# MGC3130_Board.net
KiCad netlist of a schematic drawn in EAGLE
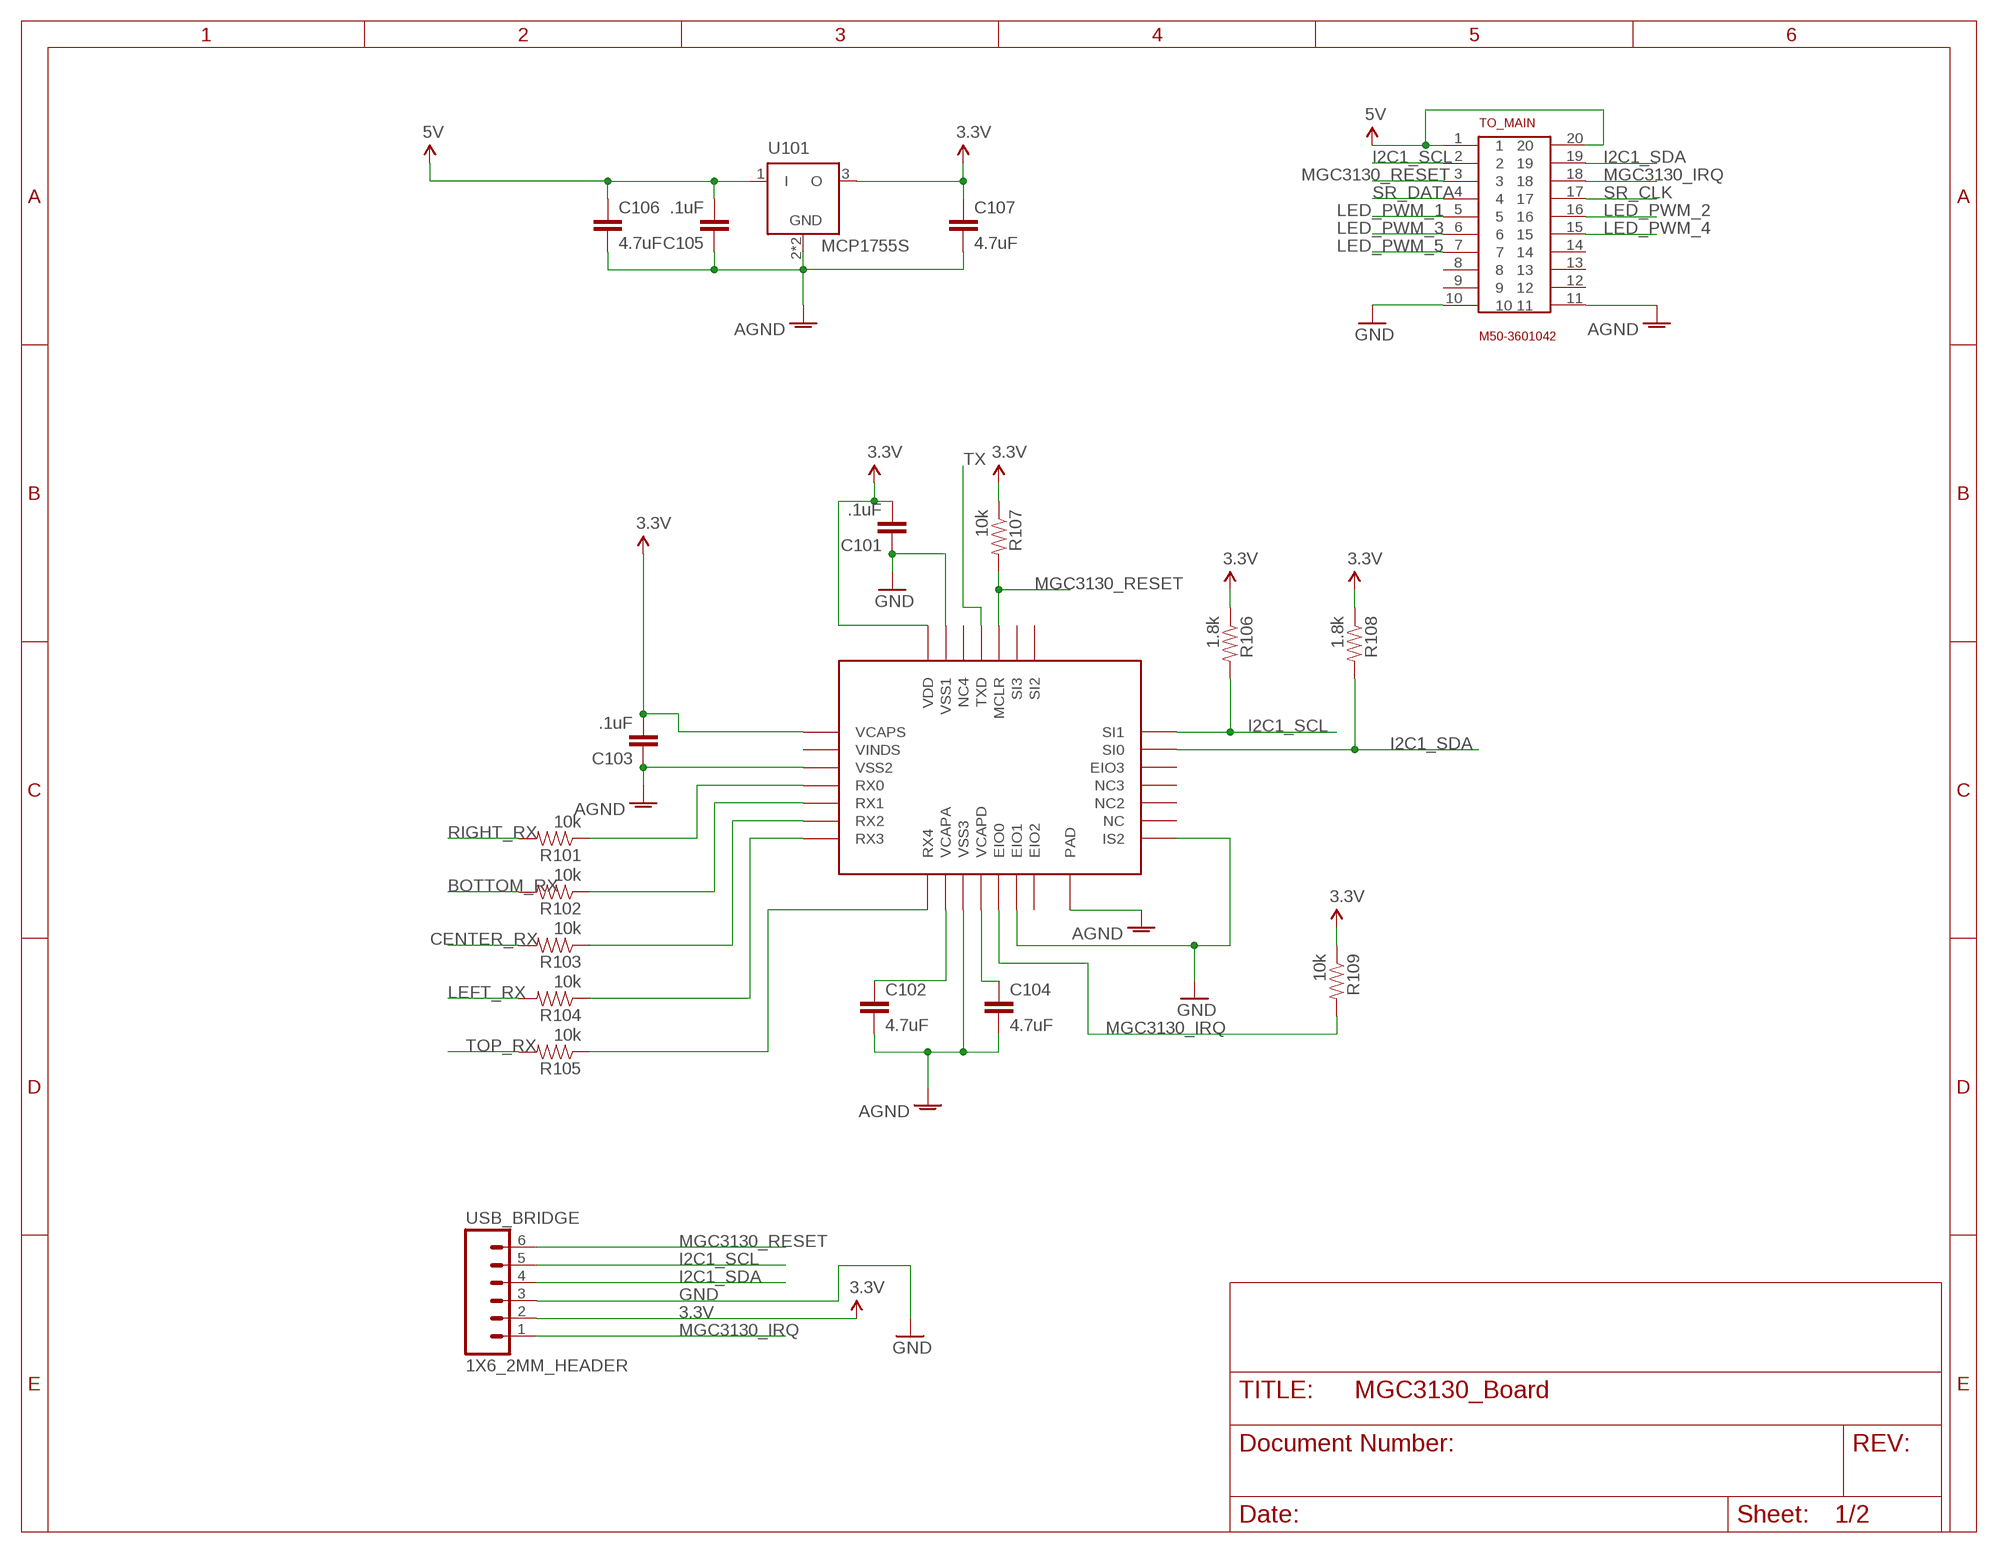
[diagram p0: schematic, sheet 1]
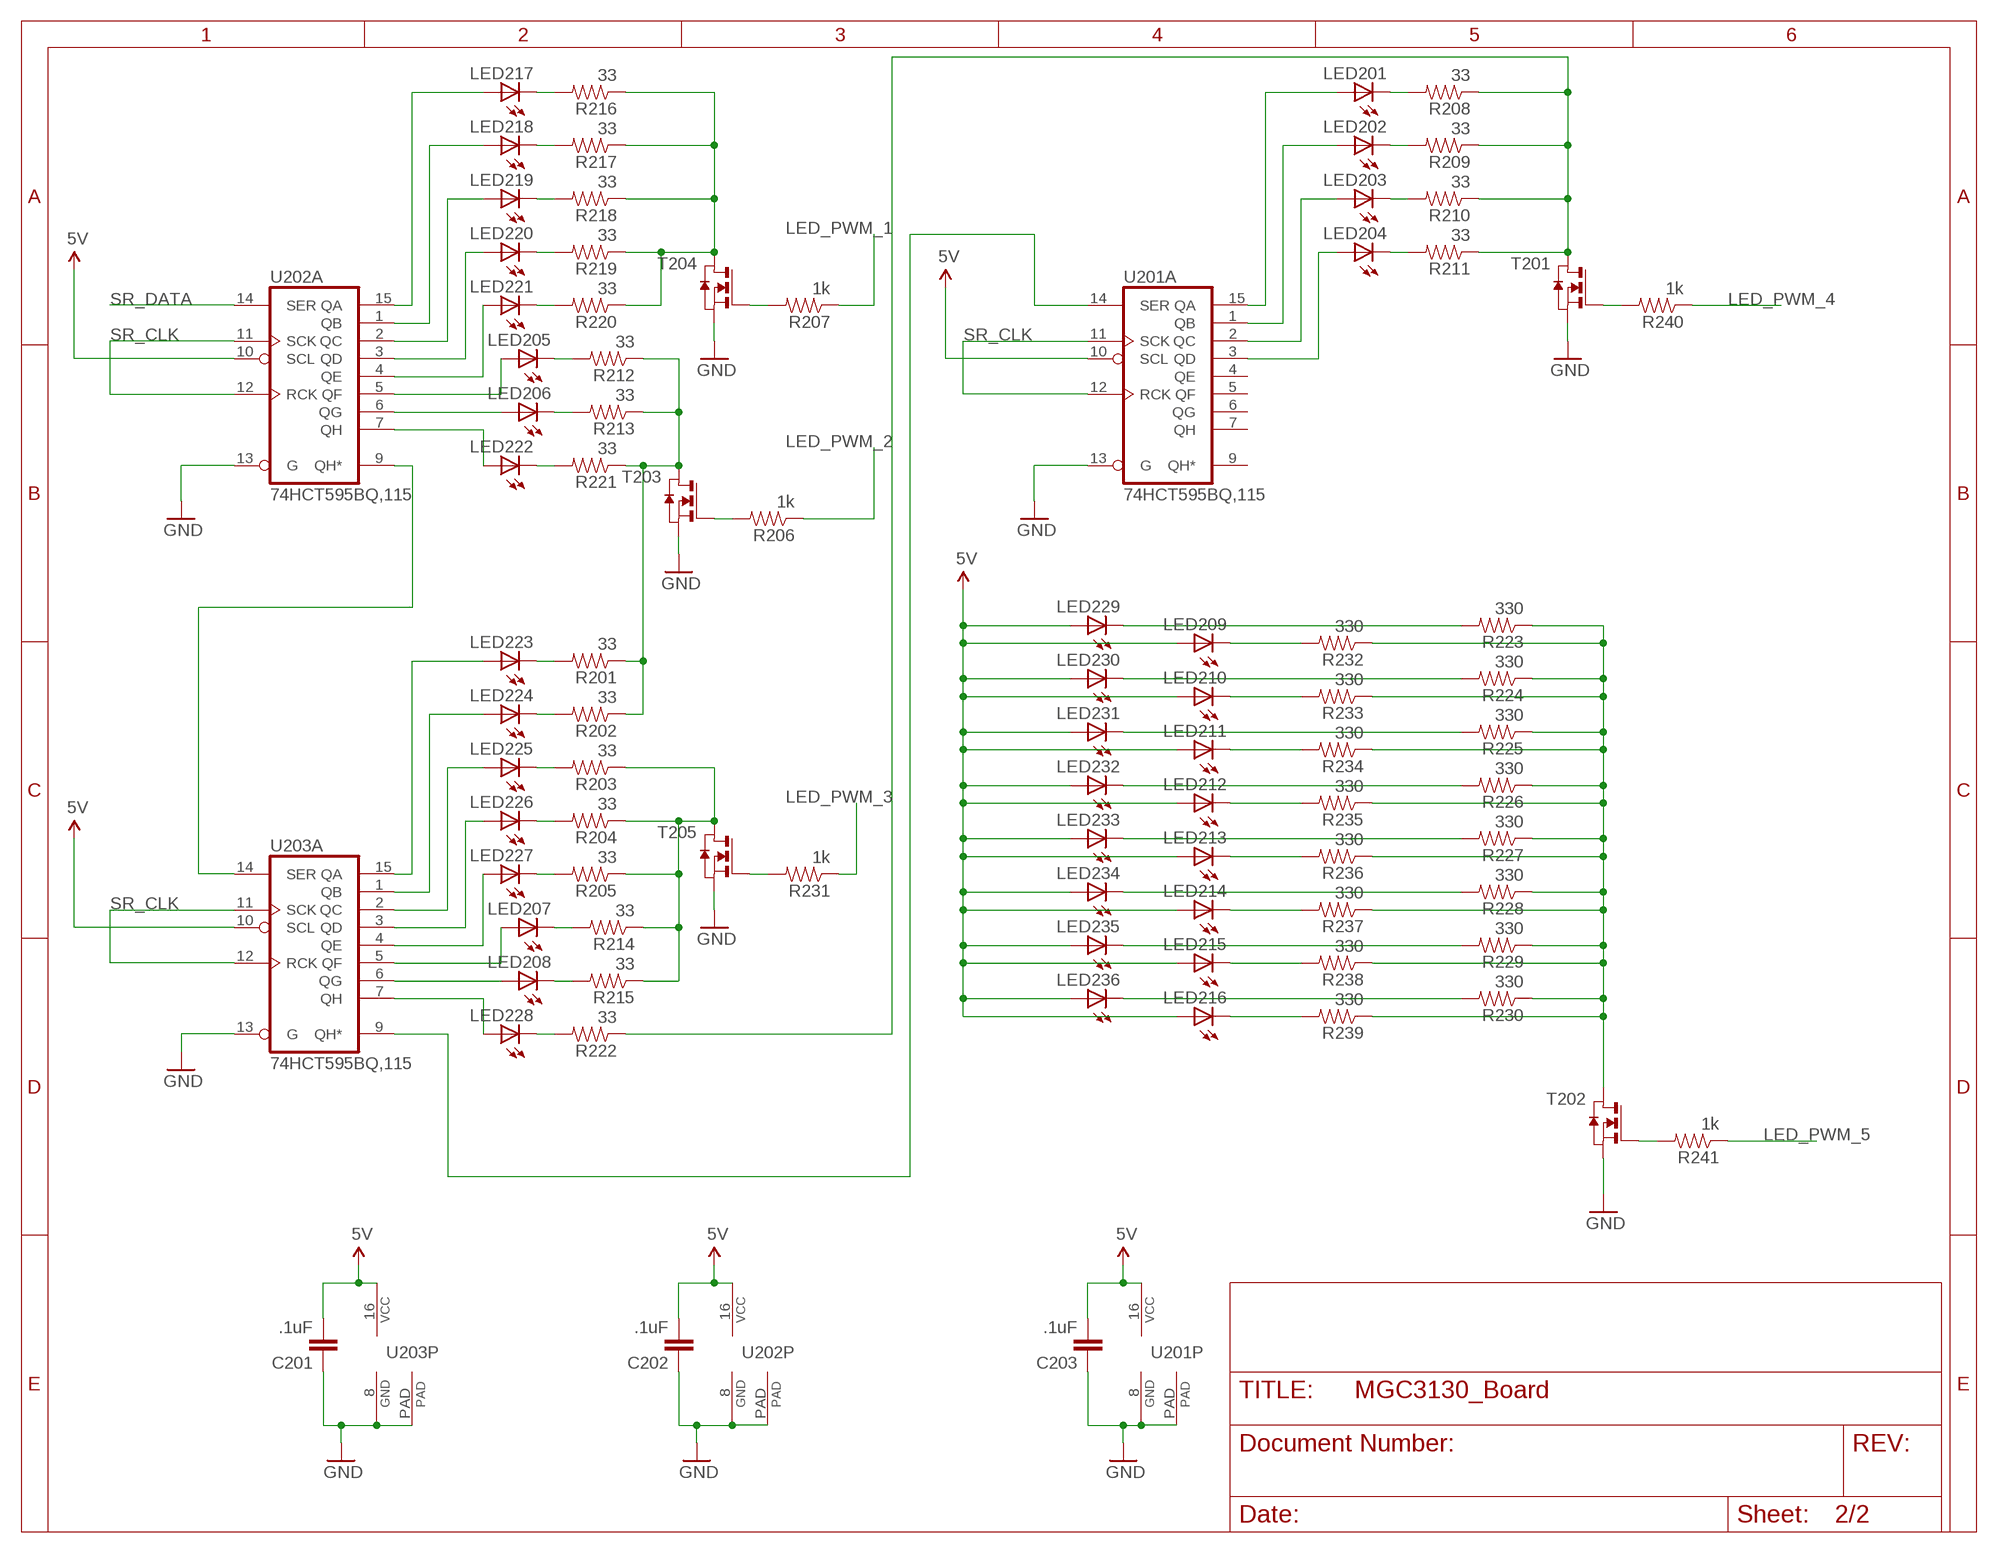
[diagram p1: schematic, sheet 2]

(export (version "E")
  (design (tool "Eeschema 10.0.6"))
  (components
    (comp (ref "C201")
      (value ".1uF")
      (footprint "eagle-import:0402-CAP")
      (libsource (lib "eagle-import") (part "CAP0402-CAP"))
    )
    (comp (ref "C202")
      (value ".1uF")
      (footprint "eagle-import:0402-CAP")
      (libsource (lib "eagle-import") (part "CAP0402-CAP"))
    )
    (comp (ref "C203")
      (value ".1uF")
      (footprint "eagle-import:0402-CAP")
      (libsource (lib "eagle-import") (part "CAP0402-CAP"))
    )
    (comp (ref "LED201")
      (value "APA3010QBC/D-GX")
      (footprint "eagle-import:APA3010")
      (libsource (lib "eagle-import") (part "APA3010QBC/D-GX"))
    )
    (comp (ref "LED202")
      (value "APA3010QBC/D-GX")
      (footprint "eagle-import:APA3010")
      (libsource (lib "eagle-import") (part "APA3010QBC/D-GX"))
    )
    (comp (ref "LED203")
      (value "APA3010QBC/D-GX")
      (footprint "eagle-import:APA3010")
      (libsource (lib "eagle-import") (part "APA3010QBC/D-GX"))
    )
    (comp (ref "LED204")
      (value "APA3010QBC/D-GX")
      (footprint "eagle-import:APA3010")
      (libsource (lib "eagle-import") (part "APA3010QBC/D-GX"))
    )
    (comp (ref "LED205")
      (value "APA3010QBC/D-GX")
      (footprint "eagle-import:APA3010")
      (libsource (lib "eagle-import") (part "APA3010QBC/D-GX"))
    )
    (comp (ref "LED206")
      (value "APA3010QBC/D-GX")
      (footprint "eagle-import:APA3010")
      (libsource (lib "eagle-import") (part "APA3010QBC/D-GX"))
    )
    (comp (ref "LED207")
      (value "APA3010QBC/D-GX")
      (footprint "eagle-import:APA3010")
      (libsource (lib "eagle-import") (part "APA3010QBC/D-GX"))
    )
    (comp (ref "LED208")
      (value "APA3010QBC/D-GX")
      (footprint "eagle-import:APA3010")
      (libsource (lib "eagle-import") (part "APA3010QBC/D-GX"))
    )
    (comp (ref "LED209")
      (value "APA3010SRCPRV-GX")
      (footprint "eagle-import:APA3010")
      (libsource (lib "eagle-import") (part "APA3010SRCPRV-GX"))
    )
    (comp (ref "LED210")
      (value "APA3010SRCPRV-GX")
      (footprint "eagle-import:APA3010")
      (libsource (lib "eagle-import") (part "APA3010SRCPRV-GX"))
    )
    (comp (ref "LED211")
      (value "APA3010SRCPRV-GX")
      (footprint "eagle-import:APA3010")
      (libsource (lib "eagle-import") (part "APA3010SRCPRV-GX"))
    )
    (comp (ref "LED212")
      (value "APA3010SRCPRV-GX")
      (footprint "eagle-import:APA3010")
      (libsource (lib "eagle-import") (part "APA3010SRCPRV-GX"))
    )
    (comp (ref "LED213")
      (value "APA3010SRCPRV-GX")
      (footprint "eagle-import:APA3010")
      (libsource (lib "eagle-import") (part "APA3010SRCPRV-GX"))
    )
    (comp (ref "LED214")
      (value "APA3010SRCPRV-GX")
      (footprint "eagle-import:APA3010")
      (libsource (lib "eagle-import") (part "APA3010SRCPRV-GX"))
    )
    (comp (ref "LED215")
      (value "APA3010SRCPRV-GX")
      (footprint "eagle-import:APA3010")
      (libsource (lib "eagle-import") (part "APA3010SRCPRV-GX"))
    )
    (comp (ref "LED216")
      (value "APA3010SRCPRV-GX")
      (footprint "eagle-import:APA3010")
      (libsource (lib "eagle-import") (part "APA3010SRCPRV-GX"))
    )
    (comp (ref "LED217")
      (value "APA3010QBC/D-GX")
      (footprint "eagle-import:APA3010")
      (libsource (lib "eagle-import") (part "APA3010QBC/D-GX"))
    )
    (comp (ref "LED218")
      (value "APA3010QBC/D-GX")
      (footprint "eagle-import:APA3010")
      (libsource (lib "eagle-import") (part "APA3010QBC/D-GX"))
    )
    (comp (ref "LED219")
      (value "APA3010QBC/D-GX")
      (footprint "eagle-import:APA3010")
      (libsource (lib "eagle-import") (part "APA3010QBC/D-GX"))
    )
    (comp (ref "LED220")
      (value "APA3010QBC/D-GX")
      (footprint "eagle-import:APA3010")
      (libsource (lib "eagle-import") (part "APA3010QBC/D-GX"))
    )
    (comp (ref "LED221")
      (value "APA3010QBC/D-GX")
      (footprint "eagle-import:APA3010")
      (libsource (lib "eagle-import") (part "APA3010QBC/D-GX"))
    )
    (comp (ref "LED222")
      (value "APA3010QBC/D-GX")
      (footprint "eagle-import:APA3010")
      (libsource (lib "eagle-import") (part "APA3010QBC/D-GX"))
    )
    (comp (ref "LED223")
      (value "APA3010QBC/D-GX")
      (footprint "eagle-import:APA3010")
      (libsource (lib "eagle-import") (part "APA3010QBC/D-GX"))
    )
    (comp (ref "LED224")
      (value "APA3010QBC/D-GX")
      (footprint "eagle-import:APA3010")
      (libsource (lib "eagle-import") (part "APA3010QBC/D-GX"))
    )
    (comp (ref "LED225")
      (value "APA3010QBC/D-GX")
      (footprint "eagle-import:APA3010")
      (libsource (lib "eagle-import") (part "APA3010QBC/D-GX"))
    )
    (comp (ref "LED226")
      (value "APA3010QBC/D-GX")
      (footprint "eagle-import:APA3010")
      (libsource (lib "eagle-import") (part "APA3010QBC/D-GX"))
    )
    (comp (ref "LED227")
      (value "APA3010QBC/D-GX")
      (footprint "eagle-import:APA3010")
      (libsource (lib "eagle-import") (part "APA3010QBC/D-GX"))
    )
    (comp (ref "LED228")
      (value "APA3010QBC/D-GX")
      (footprint "eagle-import:APA3010")
      (libsource (lib "eagle-import") (part "APA3010QBC/D-GX"))
    )
    (comp (ref "LED229")
      (value "APA3010SRCPRV-GX")
      (footprint "eagle-import:APA3010")
      (libsource (lib "eagle-import") (part "APA3010SRCPRV-GX"))
    )
    (comp (ref "LED230")
      (value "APA3010SRCPRV-GX")
      (footprint "eagle-import:APA3010")
      (libsource (lib "eagle-import") (part "APA3010SRCPRV-GX"))
    )
    (comp (ref "LED231")
      (value "APA3010SRCPRV-GX")
      (footprint "eagle-import:APA3010")
      (libsource (lib "eagle-import") (part "APA3010SRCPRV-GX"))
    )
    (comp (ref "LED232")
      (value "APA3010SRCPRV-GX")
      (footprint "eagle-import:APA3010")
      (libsource (lib "eagle-import") (part "APA3010SRCPRV-GX"))
    )
    (comp (ref "LED233")
      (value "APA3010SRCPRV-GX")
      (footprint "eagle-import:APA3010")
      (libsource (lib "eagle-import") (part "APA3010SRCPRV-GX"))
    )
    (comp (ref "LED234")
      (value "APA3010SRCPRV-GX")
      (footprint "eagle-import:APA3010")
      (libsource (lib "eagle-import") (part "APA3010SRCPRV-GX"))
    )
    (comp (ref "LED235")
      (value "APA3010SRCPRV-GX")
      (footprint "eagle-import:APA3010")
      (libsource (lib "eagle-import") (part "APA3010SRCPRV-GX"))
    )
    (comp (ref "LED236")
      (value "APA3010SRCPRV-GX")
      (footprint "eagle-import:APA3010")
      (libsource (lib "eagle-import") (part "APA3010SRCPRV-GX"))
    )
    (comp (ref "R201")
      (value "33")
      (footprint "eagle-import:0402-RES")
      (libsource (lib "eagle-import") (part "RESISTOR0402-RES"))
    )
    (comp (ref "R202")
      (value "33")
      (footprint "eagle-import:0402-RES")
      (libsource (lib "eagle-import") (part "RESISTOR0402-RES"))
    )
    (comp (ref "R203")
      (value "33")
      (footprint "eagle-import:0402-RES")
      (libsource (lib "eagle-import") (part "RESISTOR0402-RES"))
    )
    (comp (ref "R204")
      (value "33")
      (footprint "eagle-import:0402-RES")
      (libsource (lib "eagle-import") (part "RESISTOR0402-RES"))
    )
    (comp (ref "R205")
      (value "33")
      (footprint "eagle-import:0402-RES")
      (libsource (lib "eagle-import") (part "RESISTOR0402-RES"))
    )
    (comp (ref "R206")
      (value "1k")
      (footprint "eagle-import:0402-RES")
      (libsource (lib "eagle-import") (part "RESISTOR0402-RES"))
    )
    (comp (ref "R207")
      (value "1k")
      (footprint "eagle-import:0402-RES")
      (libsource (lib "eagle-import") (part "RESISTOR0402-RES"))
    )
    (comp (ref "R208")
      (value "33")
      (footprint "eagle-import:0402-RES")
      (libsource (lib "eagle-import") (part "RESISTOR0402-RES"))
    )
    (comp (ref "R209")
      (value "33")
      (footprint "eagle-import:0402-RES")
      (libsource (lib "eagle-import") (part "RESISTOR0402-RES"))
    )
    (comp (ref "R210")
      (value "33")
      (footprint "eagle-import:0402-RES")
      (libsource (lib "eagle-import") (part "RESISTOR0402-RES"))
    )
    (comp (ref "R211")
      (value "33")
      (footprint "eagle-import:0402-RES")
      (libsource (lib "eagle-import") (part "RESISTOR0402-RES"))
    )
    (comp (ref "R212")
      (value "33")
      (footprint "eagle-import:0402-RES")
      (libsource (lib "eagle-import") (part "RESISTOR0402-RES"))
    )
    (comp (ref "R213")
      (value "33")
      (footprint "eagle-import:0402-RES")
      (libsource (lib "eagle-import") (part "RESISTOR0402-RES"))
    )
    (comp (ref "R214")
      (value "33")
      (footprint "eagle-import:0402-RES")
      (libsource (lib "eagle-import") (part "RESISTOR0402-RES"))
    )
    (comp (ref "R215")
      (value "33")
      (footprint "eagle-import:0402-RES")
      (libsource (lib "eagle-import") (part "RESISTOR0402-RES"))
    )
    (comp (ref "R216")
      (value "33")
      (footprint "eagle-import:0402-RES")
      (libsource (lib "eagle-import") (part "RESISTOR0402-RES"))
    )
    (comp (ref "R217")
      (value "33")
      (footprint "eagle-import:0402-RES")
      (libsource (lib "eagle-import") (part "RESISTOR0402-RES"))
    )
    (comp (ref "R218")
      (value "33")
      (footprint "eagle-import:0402-RES")
      (libsource (lib "eagle-import") (part "RESISTOR0402-RES"))
    )
    (comp (ref "R219")
      (value "33")
      (footprint "eagle-import:0402-RES")
      (libsource (lib "eagle-import") (part "RESISTOR0402-RES"))
    )
    (comp (ref "R220")
      (value "33")
      (footprint "eagle-import:0402-RES")
      (libsource (lib "eagle-import") (part "RESISTOR0402-RES"))
    )
    (comp (ref "R221")
      (value "33")
      (footprint "eagle-import:0402-RES")
      (libsource (lib "eagle-import") (part "RESISTOR0402-RES"))
    )
    (comp (ref "R222")
      (value "33")
      (footprint "eagle-import:0402-RES")
      (libsource (lib "eagle-import") (part "RESISTOR0402-RES"))
    )
    (comp (ref "R223")
      (value "330")
      (footprint "eagle-import:0402-RES")
      (libsource (lib "eagle-import") (part "RESISTOR0402-RES"))
    )
    (comp (ref "R224")
      (value "330")
      (footprint "eagle-import:0402-RES")
      (libsource (lib "eagle-import") (part "RESISTOR0402-RES"))
    )
    (comp (ref "R225")
      (value "330")
      (footprint "eagle-import:0402-RES")
      (libsource (lib "eagle-import") (part "RESISTOR0402-RES"))
    )
    (comp (ref "R226")
      (value "330")
      (footprint "eagle-import:0402-RES")
      (libsource (lib "eagle-import") (part "RESISTOR0402-RES"))
    )
    (comp (ref "R227")
      (value "330")
      (footprint "eagle-import:0402-RES")
      (libsource (lib "eagle-import") (part "RESISTOR0402-RES"))
    )
    (comp (ref "R228")
      (value "330")
      (footprint "eagle-import:0402-RES")
      (libsource (lib "eagle-import") (part "RESISTOR0402-RES"))
    )
    (comp (ref "R229")
      (value "330")
      (footprint "eagle-import:0402-RES")
      (libsource (lib "eagle-import") (part "RESISTOR0402-RES"))
    )
    (comp (ref "R230")
      (value "330")
      (footprint "eagle-import:0402-RES")
      (libsource (lib "eagle-import") (part "RESISTOR0402-RES"))
    )
    (comp (ref "R231")
      (value "1k")
      (footprint "eagle-import:0402-RES")
      (libsource (lib "eagle-import") (part "RESISTOR0402-RES"))
    )
    (comp (ref "R232")
      (value "330")
      (footprint "eagle-import:0402-RES")
      (libsource (lib "eagle-import") (part "RESISTOR0402-RES"))
    )
    (comp (ref "R233")
      (value "330")
      (footprint "eagle-import:0402-RES")
      (libsource (lib "eagle-import") (part "RESISTOR0402-RES"))
    )
    (comp (ref "R234")
      (value "330")
      (footprint "eagle-import:0402-RES")
      (libsource (lib "eagle-import") (part "RESISTOR0402-RES"))
    )
    (comp (ref "R235")
      (value "330")
      (footprint "eagle-import:0402-RES")
      (libsource (lib "eagle-import") (part "RESISTOR0402-RES"))
    )
    (comp (ref "R236")
      (value "330")
      (footprint "eagle-import:0402-RES")
      (libsource (lib "eagle-import") (part "RESISTOR0402-RES"))
    )
    (comp (ref "R237")
      (value "330")
      (footprint "eagle-import:0402-RES")
      (libsource (lib "eagle-import") (part "RESISTOR0402-RES"))
    )
    (comp (ref "R238")
      (value "330")
      (footprint "eagle-import:0402-RES")
      (libsource (lib "eagle-import") (part "RESISTOR0402-RES"))
    )
    (comp (ref "R239")
      (value "330")
      (footprint "eagle-import:0402-RES")
      (libsource (lib "eagle-import") (part "RESISTOR0402-RES"))
    )
    (comp (ref "R240")
      (value "1k")
      (footprint "eagle-import:0603-RES")
      (libsource (lib "eagle-import") (part "RESISTOR0603-RES"))
    )
    (comp (ref "R241")
      (value "1k")
      (footprint "eagle-import:0402-RES")
      (libsource (lib "eagle-import") (part "RESISTOR0402-RES"))
    )
    (comp (ref "T201")
      (value "NMOSSOT23")
      (footprint "eagle-import:SOT-23")
      (libsource (lib "eagle-import") (part "NMOSSOT23"))
    )
    (comp (ref "T202")
      (value "NMOSSOT23")
      (footprint "eagle-import:SOT-23")
      (libsource (lib "eagle-import") (part "NMOSSOT23"))
    )
    (comp (ref "T203")
      (value "NMOSSOT23")
      (footprint "eagle-import:SOT-23")
      (libsource (lib "eagle-import") (part "NMOSSOT23"))
    )
    (comp (ref "T204")
      (value "NMOSSOT23")
      (footprint "eagle-import:SOT-23")
      (libsource (lib "eagle-import") (part "NMOSSOT23"))
    )
    (comp (ref "T205")
      (value "NMOSSOT23")
      (footprint "eagle-import:SOT-23")
      (libsource (lib "eagle-import") (part "NMOSSOT23"))
    )
    (comp (ref "U201")
      (value "74HCT595BQ,115")
      (footprint "eagle-import:DHVQFN16")
      (libsource (lib "eagle-import") (part "74HCT595BQ,115"))
    )
    (comp (ref "U202")
      (value "74HCT595BQ,115")
      (footprint "eagle-import:DHVQFN16")
      (libsource (lib "eagle-import") (part "74HCT595BQ,115"))
    )
    (comp (ref "U203")
      (value "74HCT595BQ,115")
      (footprint "eagle-import:DHVQFN16")
      (libsource (lib "eagle-import") (part "74HCT595BQ,115"))
    )
    (comp (ref "C101")
      (value ".1uF")
      (footprint "eagle-import:0402-CAP")
      (libsource (lib "eagle-import") (part "CAP0402-CAP"))
    )
    (comp (ref "C102")
      (value "4.7uF")
      (footprint "eagle-import:0805")
      (libsource (lib "eagle-import") (part "CAP0805"))
    )
    (comp (ref "C103")
      (value ".1uF")
      (footprint "eagle-import:0402-CAP")
      (libsource (lib "eagle-import") (part "CAP0402-CAP"))
    )
    (comp (ref "C104")
      (value "4.7uF")
      (footprint "eagle-import:0805")
      (libsource (lib "eagle-import") (part "CAP0805"))
    )
    (comp (ref "C105")
      (value ".1uF")
      (footprint "eagle-import:0402-CAP")
      (libsource (lib "eagle-import") (part "CAP0402-CAP"))
    )
    (comp (ref "C106")
      (value "4.7uF")
      (footprint "eagle-import:0805")
      (libsource (lib "eagle-import") (part "CAP0805"))
    )
    (comp (ref "C107")
      (value "4.7uF")
      (footprint "eagle-import:0805")
      (libsource (lib "eagle-import") (part "CAP0805"))
    )
    (comp (ref "R101")
      (value "10k")
      (footprint "eagle-import:0402-RES")
      (libsource (lib "eagle-import") (part "RESISTOR0402-RES"))
    )
    (comp (ref "R102")
      (value "10k")
      (footprint "eagle-import:0402-RES")
      (libsource (lib "eagle-import") (part "RESISTOR0402-RES"))
    )
    (comp (ref "R103")
      (value "10k")
      (footprint "eagle-import:0402-RES")
      (libsource (lib "eagle-import") (part "RESISTOR0402-RES"))
    )
    (comp (ref "R104")
      (value "10k")
      (footprint "eagle-import:0402-RES")
      (libsource (lib "eagle-import") (part "RESISTOR0402-RES"))
    )
    (comp (ref "R105")
      (value "10k")
      (footprint "eagle-import:0402-RES")
      (libsource (lib "eagle-import") (part "RESISTOR0402-RES"))
    )
    (comp (ref "R106")
      (value "1.8k")
      (footprint "eagle-import:0402-RES")
      (libsource (lib "eagle-import") (part "RESISTOR0402-RES"))
    )
    (comp (ref "R107")
      (value "10k")
      (footprint "eagle-import:0402-RES")
      (libsource (lib "eagle-import") (part "RESISTOR0402-RES"))
    )
    (comp (ref "R108")
      (value "1.8k")
      (footprint "eagle-import:0402-RES")
      (libsource (lib "eagle-import") (part "RESISTOR0402-RES"))
    )
    (comp (ref "R109")
      (value "10k")
      (footprint "eagle-import:0402-RES")
      (libsource (lib "eagle-import") (part "RESISTOR0402-RES"))
    )
    (comp (ref "TO_MAIN")
      (value "M50-3601042")
      (footprint "eagle-import:M50-3601042")
      (libsource (lib "eagle-import") (part "M50-3601042"))
    )
    (comp (ref "U101")
      (value "MCP1755S")
      (footprint "eagle-import:SOT223")
      (libsource (lib "eagle-import") (part "MCP1755S"))
    )
    (comp (ref "U102")
      (value "MGC3130")
      (footprint "eagle-import:QFN28")
      (libsource (lib "eagle-import") (part "MGC3130"))
    )
    (comp (ref "USB_BRIDGE")
      (value "1X6_2MM_HEADER")
      (footprint "eagle-import:1X6_2MM_HEADER")
      (libsource (lib "eagle-import") (part "1X6_2MM_HEADER"))
    )
  )
  (nets
    (net (code "1") (name "3.3V") (class "Default")
      (node (ref "C101") (pin "2") (pinfunction "2_2") (pintype "passive"))
      (node (ref "C103") (pin "2") (pinfunction "2_2") (pintype "passive"))
      (node (ref "C107") (pin "1") (pinfunction "1_1") (pintype "passive"))
      (node (ref "R106") (pin "1") (pinfunction "1_1") (pintype "passive"))
      (node (ref "R107") (pin "1") (pinfunction "1_1") (pintype "passive"))
      (node (ref "R108") (pin "1") (pinfunction "1_1") (pintype "passive"))
      (node (ref "R109") (pin "1") (pinfunction "1_1") (pintype "passive"))
      (node (ref "U101") (pin "3") (pinfunction "O_3") (pintype "input"))
      (node (ref "U102") (pin "P$1") (pinfunction "VCAPS_P$1") (pintype "bidirectional"))
      (node (ref "U102") (pin "P$28") (pinfunction "VDD_P$28") (pintype "bidirectional"))
      (node (ref "USB_BRIDGE") (pin "2") (pinfunction "2_2") (pintype "passive"))
    )
    (net (code "2") (name "5V") (class "Default")
      (node (ref "C105") (pin "2") (pinfunction "2_2") (pintype "passive"))
      (node (ref "C106") (pin "1") (pinfunction "1_1") (pintype "passive"))
      (node (ref "C201") (pin "2") (pinfunction "2_2") (pintype "passive"))
      (node (ref "C202") (pin "2") (pinfunction "2_2") (pintype "passive"))
      (node (ref "C203") (pin "2") (pinfunction "2_2") (pintype "passive"))
      (node (ref "LED209") (pin "P$2") (pinfunction "A_P$2") (pintype "passive"))
      (node (ref "LED210") (pin "P$2") (pinfunction "A_P$2") (pintype "passive"))
      (node (ref "LED211") (pin "P$2") (pinfunction "A_P$2") (pintype "passive"))
      (node (ref "LED212") (pin "P$2") (pinfunction "A_P$2") (pintype "passive"))
      (node (ref "LED213") (pin "P$2") (pinfunction "A_P$2") (pintype "passive"))
      (node (ref "LED214") (pin "P$2") (pinfunction "A_P$2") (pintype "passive"))
      (node (ref "LED215") (pin "P$2") (pinfunction "A_P$2") (pintype "passive"))
      (node (ref "LED216") (pin "P$2") (pinfunction "A_P$2") (pintype "passive"))
      (node (ref "LED229") (pin "P$2") (pinfunction "A_P$2") (pintype "passive"))
      (node (ref "LED230") (pin "P$2") (pinfunction "A_P$2") (pintype "passive"))
      (node (ref "LED231") (pin "P$2") (pinfunction "A_P$2") (pintype "passive"))
      (node (ref "LED232") (pin "P$2") (pinfunction "A_P$2") (pintype "passive"))
      (node (ref "LED233") (pin "P$2") (pinfunction "A_P$2") (pintype "passive"))
      (node (ref "LED234") (pin "P$2") (pinfunction "A_P$2") (pintype "passive"))
      (node (ref "LED235") (pin "P$2") (pinfunction "A_P$2") (pintype "passive"))
      (node (ref "LED236") (pin "P$2") (pinfunction "A_P$2") (pintype "passive"))
      (node (ref "TO_MAIN") (pin "1") (pinfunction "1_1") (pintype "bidirectional"))
      (node (ref "TO_MAIN") (pin "20") (pinfunction "20_20") (pintype "bidirectional"))
      (node (ref "U101") (pin "1") (pinfunction "I_1") (pintype "input"))
      (node (ref "U201") (pin "10") (pinfunction "SCL_10") (pintype "input"))
      (node (ref "U201") (pin "16") (pinfunction "VCC_16") (pintype "power_in"))
      (node (ref "U202") (pin "10") (pinfunction "SCL_10") (pintype "input"))
      (node (ref "U202") (pin "16") (pinfunction "VCC_16") (pintype "power_in"))
      (node (ref "U203") (pin "10") (pinfunction "SCL_10") (pintype "input"))
      (node (ref "U203") (pin "16") (pinfunction "VCC_16") (pintype "power_in"))
    )
    (net (code "3") (name "AGND") (class "Default")
      (node (ref "C102") (pin "2") (pinfunction "2_2") (pintype "passive"))
      (node (ref "C103") (pin "1") (pinfunction "1_1") (pintype "passive"))
      (node (ref "C104") (pin "2") (pinfunction "2_2") (pintype "passive"))
      (node (ref "C105") (pin "1") (pinfunction "1_1") (pintype "passive"))
      (node (ref "C106") (pin "2") (pinfunction "2_2") (pintype "passive"))
      (node (ref "C107") (pin "2") (pinfunction "2_2") (pintype "passive"))
      (node (ref "TO_MAIN") (pin "11") (pinfunction "11_11") (pintype "bidirectional"))
      (node (ref "U101") (pin "2") (pinfunction "GND_2") (pintype "power_in"))
      (node (ref "U101") (pin "4") (pinfunction "GND_4") (pintype "power_in"))
      (node (ref "U102") (pin "P$10") (pinfunction "VSS3_P$10") (pintype "bidirectional"))
      (node (ref "U102") (pin "P$29") (pinfunction "PAD_P$29") (pintype "bidirectional"))
      (node (ref "U102") (pin "P$3") (pinfunction "VSS2_P$3") (pintype "bidirectional"))
    )
    (net (code "4") (name "BOTTOM_RX") (class "Default")
      (node (ref "R102") (pin "2") (pinfunction "2_2") (pintype "passive"))
    )
    (net (code "5") (name "CENTER_RX") (class "Default")
      (node (ref "R103") (pin "2") (pinfunction "2_2") (pintype "passive"))
    )
    (net (code "6") (name "GND") (class "Default")
      (node (ref "C101") (pin "1") (pinfunction "1_1") (pintype "passive"))
      (node (ref "C201") (pin "1") (pinfunction "1_1") (pintype "passive"))
      (node (ref "C202") (pin "1") (pinfunction "1_1") (pintype "passive"))
      (node (ref "C203") (pin "1") (pinfunction "1_1") (pintype "passive"))
      (node (ref "T201") (pin "2") (pinfunction "S_2") (pintype "passive"))
      (node (ref "T202") (pin "2") (pinfunction "S_2") (pintype "passive"))
      (node (ref "T203") (pin "2") (pinfunction "S_2") (pintype "passive"))
      (node (ref "T204") (pin "2") (pinfunction "S_2") (pintype "passive"))
      (node (ref "T205") (pin "2") (pinfunction "S_2") (pintype "passive"))
      (node (ref "TO_MAIN") (pin "10") (pinfunction "10_10") (pintype "bidirectional"))
      (node (ref "U102") (pin "P$13") (pinfunction "EIO1_P$13") (pintype "bidirectional"))
      (node (ref "U102") (pin "P$15") (pinfunction "IS2_P$15") (pintype "bidirectional"))
      (node (ref "U102") (pin "P$27") (pinfunction "VSS1_P$27") (pintype "bidirectional"))
      (node (ref "U201") (pin "13") (pinfunction "G_13") (pintype "input"))
      (node (ref "U201") (pin "8") (pinfunction "GND_8") (pintype "power_in"))
      (node (ref "U201") (pin "PAD") (pinfunction "GND1_PAD") (pintype "power_in"))
      (node (ref "U202") (pin "13") (pinfunction "G_13") (pintype "input"))
      (node (ref "U202") (pin "8") (pinfunction "GND_8") (pintype "power_in"))
      (node (ref "U202") (pin "PAD") (pinfunction "GND1_PAD") (pintype "power_in"))
      (node (ref "U203") (pin "13") (pinfunction "G_13") (pintype "input"))
      (node (ref "U203") (pin "8") (pinfunction "GND_8") (pintype "power_in"))
      (node (ref "U203") (pin "PAD") (pinfunction "GND1_PAD") (pintype "power_in"))
      (node (ref "USB_BRIDGE") (pin "3") (pinfunction "3_3") (pintype "passive"))
    )
    (net (code "7") (name "I2C1_SCL") (class "Default")
      (node (ref "R106") (pin "2") (pinfunction "2_2") (pintype "passive"))
      (node (ref "TO_MAIN") (pin "2") (pinfunction "2_2") (pintype "bidirectional"))
      (node (ref "U102") (pin "P$21") (pinfunction "SI1_P$21") (pintype "bidirectional"))
      (node (ref "USB_BRIDGE") (pin "5") (pinfunction "5_5") (pintype "passive"))
    )
    (net (code "8") (name "I2C1_SDA") (class "Default")
      (node (ref "R108") (pin "2") (pinfunction "2_2") (pintype "passive"))
      (node (ref "TO_MAIN") (pin "19") (pinfunction "19_19") (pintype "bidirectional"))
      (node (ref "U102") (pin "P$20") (pinfunction "SI0_P$20") (pintype "bidirectional"))
      (node (ref "USB_BRIDGE") (pin "4") (pinfunction "4_4") (pintype "passive"))
    )
    (net (code "9") (name "LED_PWM_1") (class "Default")
      (node (ref "R207") (pin "1") (pinfunction "1_1") (pintype "passive"))
      (node (ref "TO_MAIN") (pin "5") (pinfunction "5_5") (pintype "bidirectional"))
    )
    (net (code "10") (name "LED_PWM_2") (class "Default")
      (node (ref "R206") (pin "1") (pinfunction "1_1") (pintype "passive"))
      (node (ref "TO_MAIN") (pin "16") (pinfunction "16_16") (pintype "bidirectional"))
    )
    (net (code "11") (name "LED_PWM_3") (class "Default")
      (node (ref "R231") (pin "1") (pinfunction "1_1") (pintype "passive"))
      (node (ref "TO_MAIN") (pin "6") (pinfunction "6_6") (pintype "bidirectional"))
    )
    (net (code "12") (name "LED_PWM_4") (class "Default")
      (node (ref "R240") (pin "1") (pinfunction "1_1") (pintype "passive"))
      (node (ref "TO_MAIN") (pin "15") (pinfunction "15_15") (pintype "bidirectional"))
    )
    (net (code "13") (name "LED_PWM_5") (class "Default")
      (node (ref "R241") (pin "1") (pinfunction "1_1") (pintype "passive"))
      (node (ref "TO_MAIN") (pin "7") (pinfunction "7_7") (pintype "bidirectional"))
    )
    (net (code "14") (name "LEFT_RX") (class "Default")
      (node (ref "R104") (pin "2") (pinfunction "2_2") (pintype "passive"))
    )
    (net (code "15") (name "MGC3130_IRQ") (class "Default")
      (node (ref "R109") (pin "2") (pinfunction "2_2") (pintype "passive"))
      (node (ref "TO_MAIN") (pin "18") (pinfunction "18_18") (pintype "bidirectional"))
      (node (ref "U102") (pin "P$12") (pinfunction "EIO0_P$12") (pintype "bidirectional"))
      (node (ref "USB_BRIDGE") (pin "1") (pinfunction "1_1") (pintype "passive"))
    )
    (net (code "16") (name "MGC3130_RESET") (class "Default")
      (node (ref "R107") (pin "2") (pinfunction "2_2") (pintype "passive"))
      (node (ref "TO_MAIN") (pin "3") (pinfunction "3_3") (pintype "bidirectional"))
      (node (ref "U102") (pin "P$24") (pinfunction "MCLR_P$24") (pintype "bidirectional"))
      (node (ref "USB_BRIDGE") (pin "6") (pinfunction "6_6") (pintype "passive"))
    )
    (net (code "17") (name "Net-(LED201-A)") (class "Default")
      (node (ref "LED201") (pin "P$2") (pinfunction "A_P$2") (pintype "passive"))
      (node (ref "U201") (pin "15") (pinfunction "QA_15") (pintype "tri_state"))
    )
    (net (code "18") (name "Net-(LED201-C)") (class "Default")
      (node (ref "LED201") (pin "P$1") (pinfunction "C_P$1") (pintype "passive"))
      (node (ref "R208") (pin "2") (pinfunction "2_2") (pintype "passive"))
    )
    (net (code "19") (name "Net-(LED202-A)") (class "Default")
      (node (ref "LED202") (pin "P$2") (pinfunction "A_P$2") (pintype "passive"))
      (node (ref "U201") (pin "1") (pinfunction "QB_1") (pintype "tri_state"))
    )
    (net (code "20") (name "Net-(LED202-C)") (class "Default")
      (node (ref "LED202") (pin "P$1") (pinfunction "C_P$1") (pintype "passive"))
      (node (ref "R209") (pin "2") (pinfunction "2_2") (pintype "passive"))
    )
    (net (code "21") (name "Net-(LED203-A)") (class "Default")
      (node (ref "LED203") (pin "P$2") (pinfunction "A_P$2") (pintype "passive"))
      (node (ref "U201") (pin "2") (pinfunction "QC_2") (pintype "tri_state"))
    )
    (net (code "22") (name "Net-(LED203-C)") (class "Default")
      (node (ref "LED203") (pin "P$1") (pinfunction "C_P$1") (pintype "passive"))
      (node (ref "R210") (pin "2") (pinfunction "2_2") (pintype "passive"))
    )
    (net (code "23") (name "Net-(LED204-A)") (class "Default")
      (node (ref "LED204") (pin "P$2") (pinfunction "A_P$2") (pintype "passive"))
      (node (ref "U201") (pin "3") (pinfunction "QD_3") (pintype "tri_state"))
    )
    (net (code "24") (name "Net-(LED204-C)") (class "Default")
      (node (ref "LED204") (pin "P$1") (pinfunction "C_P$1") (pintype "passive"))
      (node (ref "R211") (pin "2") (pinfunction "2_2") (pintype "passive"))
    )
    (net (code "25") (name "Net-(LED205-A)") (class "Default")
      (node (ref "LED205") (pin "P$2") (pinfunction "A_P$2") (pintype "passive"))
      (node (ref "U202") (pin "5") (pinfunction "QF_5") (pintype "tri_state"))
    )
    (net (code "26") (name "Net-(LED205-C)") (class "Default")
      (node (ref "LED205") (pin "P$1") (pinfunction "C_P$1") (pintype "passive"))
      (node (ref "R212") (pin "2") (pinfunction "2_2") (pintype "passive"))
    )
    (net (code "27") (name "Net-(LED206-A)") (class "Default")
      (node (ref "LED206") (pin "P$2") (pinfunction "A_P$2") (pintype "passive"))
      (node (ref "U202") (pin "6") (pinfunction "QG_6") (pintype "tri_state"))
    )
    (net (code "28") (name "Net-(LED206-C)") (class "Default")
      (node (ref "LED206") (pin "P$1") (pinfunction "C_P$1") (pintype "passive"))
      (node (ref "R213") (pin "2") (pinfunction "2_2") (pintype "passive"))
    )
    (net (code "29") (name "Net-(LED207-A)") (class "Default")
      (node (ref "LED207") (pin "P$2") (pinfunction "A_P$2") (pintype "passive"))
      (node (ref "U203") (pin "5") (pinfunction "QF_5") (pintype "tri_state"))
    )
    (net (code "30") (name "Net-(LED207-C)") (class "Default")
      (node (ref "LED207") (pin "P$1") (pinfunction "C_P$1") (pintype "passive"))
      (node (ref "R214") (pin "2") (pinfunction "2_2") (pintype "passive"))
    )
    (net (code "31") (name "Net-(LED208-A)") (class "Default")
      (node (ref "LED208") (pin "P$2") (pinfunction "A_P$2") (pintype "passive"))
      (node (ref "U203") (pin "6") (pinfunction "QG_6") (pintype "tri_state"))
    )
    (net (code "32") (name "Net-(LED208-C)") (class "Default")
      (node (ref "LED208") (pin "P$1") (pinfunction "C_P$1") (pintype "passive"))
      (node (ref "R215") (pin "2") (pinfunction "2_2") (pintype "passive"))
    )
    (net (code "33") (name "Net-(LED209-C)") (class "Default")
      (node (ref "LED209") (pin "P$1") (pinfunction "C_P$1") (pintype "passive"))
      (node (ref "R232") (pin "2") (pinfunction "2_2") (pintype "passive"))
    )
    (net (code "34") (name "Net-(LED210-C)") (class "Default")
      (node (ref "LED210") (pin "P$1") (pinfunction "C_P$1") (pintype "passive"))
      (node (ref "R233") (pin "2") (pinfunction "2_2") (pintype "passive"))
    )
    (net (code "35") (name "Net-(LED211-C)") (class "Default")
      (node (ref "LED211") (pin "P$1") (pinfunction "C_P$1") (pintype "passive"))
      (node (ref "R234") (pin "2") (pinfunction "2_2") (pintype "passive"))
    )
    (net (code "36") (name "Net-(LED212-C)") (class "Default")
      (node (ref "LED212") (pin "P$1") (pinfunction "C_P$1") (pintype "passive"))
      (node (ref "R235") (pin "2") (pinfunction "2_2") (pintype "passive"))
    )
    (net (code "37") (name "Net-(LED213-C)") (class "Default")
      (node (ref "LED213") (pin "P$1") (pinfunction "C_P$1") (pintype "passive"))
      (node (ref "R236") (pin "2") (pinfunction "2_2") (pintype "passive"))
    )
    (net (code "38") (name "Net-(LED214-C)") (class "Default")
      (node (ref "LED214") (pin "P$1") (pinfunction "C_P$1") (pintype "passive"))
      (node (ref "R237") (pin "2") (pinfunction "2_2") (pintype "passive"))
    )
    (net (code "39") (name "Net-(LED215-C)") (class "Default")
      (node (ref "LED215") (pin "P$1") (pinfunction "C_P$1") (pintype "passive"))
      (node (ref "R238") (pin "2") (pinfunction "2_2") (pintype "passive"))
    )
    (net (code "40") (name "Net-(LED216-C)") (class "Default")
      (node (ref "LED216") (pin "P$1") (pinfunction "C_P$1") (pintype "passive"))
      (node (ref "R239") (pin "2") (pinfunction "2_2") (pintype "passive"))
    )
    (net (code "41") (name "Net-(LED217-A)") (class "Default")
      (node (ref "LED217") (pin "P$2") (pinfunction "A_P$2") (pintype "passive"))
      (node (ref "U202") (pin "15") (pinfunction "QA_15") (pintype "tri_state"))
    )
    (net (code "42") (name "Net-(LED217-C)") (class "Default")
      (node (ref "LED217") (pin "P$1") (pinfunction "C_P$1") (pintype "passive"))
      (node (ref "R216") (pin "2") (pinfunction "2_2") (pintype "passive"))
    )
    (net (code "43") (name "Net-(LED218-A)") (class "Default")
      (node (ref "LED218") (pin "P$2") (pinfunction "A_P$2") (pintype "passive"))
      (node (ref "U202") (pin "1") (pinfunction "QB_1") (pintype "tri_state"))
    )
    (net (code "44") (name "Net-(LED218-C)") (class "Default")
      (node (ref "LED218") (pin "P$1") (pinfunction "C_P$1") (pintype "passive"))
      (node (ref "R217") (pin "2") (pinfunction "2_2") (pintype "passive"))
    )
    (net (code "45") (name "Net-(LED219-A)") (class "Default")
      (node (ref "LED219") (pin "P$2") (pinfunction "A_P$2") (pintype "passive"))
      (node (ref "U202") (pin "2") (pinfunction "QC_2") (pintype "tri_state"))
    )
    (net (code "46") (name "Net-(LED219-C)") (class "Default")
      (node (ref "LED219") (pin "P$1") (pinfunction "C_P$1") (pintype "passive"))
      (node (ref "R218") (pin "2") (pinfunction "2_2") (pintype "passive"))
    )
    (net (code "47") (name "Net-(LED220-A)") (class "Default")
      (node (ref "LED220") (pin "P$2") (pinfunction "A_P$2") (pintype "passive"))
      (node (ref "U202") (pin "3") (pinfunction "QD_3") (pintype "tri_state"))
    )
    (net (code "48") (name "Net-(LED220-C)") (class "Default")
      (node (ref "LED220") (pin "P$1") (pinfunction "C_P$1") (pintype "passive"))
      (node (ref "R219") (pin "2") (pinfunction "2_2") (pintype "passive"))
    )
    (net (code "49") (name "Net-(LED221-A)") (class "Default")
      (node (ref "LED221") (pin "P$2") (pinfunction "A_P$2") (pintype "passive"))
      (node (ref "U202") (pin "4") (pinfunction "QE_4") (pintype "tri_state"))
    )
    (net (code "50") (name "Net-(LED221-C)") (class "Default")
      (node (ref "LED221") (pin "P$1") (pinfunction "C_P$1") (pintype "passive"))
      (node (ref "R220") (pin "2") (pinfunction "2_2") (pintype "passive"))
    )
    (net (code "51") (name "Net-(LED222-A)") (class "Default")
      (node (ref "LED222") (pin "P$2") (pinfunction "A_P$2") (pintype "passive"))
      (node (ref "U202") (pin "7") (pinfunction "QH_7") (pintype "tri_state"))
    )
    (net (code "52") (name "Net-(LED222-C)") (class "Default")
      (node (ref "LED222") (pin "P$1") (pinfunction "C_P$1") (pintype "passive"))
      (node (ref "R221") (pin "2") (pinfunction "2_2") (pintype "passive"))
    )
    (net (code "53") (name "Net-(LED223-A)") (class "Default")
      (node (ref "LED223") (pin "P$2") (pinfunction "A_P$2") (pintype "passive"))
      (node (ref "U203") (pin "15") (pinfunction "QA_15") (pintype "tri_state"))
    )
    (net (code "54") (name "Net-(LED223-C)") (class "Default")
      (node (ref "LED223") (pin "P$1") (pinfunction "C_P$1") (pintype "passive"))
      (node (ref "R201") (pin "2") (pinfunction "2_2") (pintype "passive"))
    )
    (net (code "55") (name "Net-(LED224-A)") (class "Default")
      (node (ref "LED224") (pin "P$2") (pinfunction "A_P$2") (pintype "passive"))
      (node (ref "U203") (pin "1") (pinfunction "QB_1") (pintype "tri_state"))
    )
    (net (code "56") (name "Net-(LED224-C)") (class "Default")
      (node (ref "LED224") (pin "P$1") (pinfunction "C_P$1") (pintype "passive"))
      (node (ref "R202") (pin "2") (pinfunction "2_2") (pintype "passive"))
    )
    (net (code "57") (name "Net-(LED225-A)") (class "Default")
      (node (ref "LED225") (pin "P$2") (pinfunction "A_P$2") (pintype "passive"))
      (node (ref "U203") (pin "2") (pinfunction "QC_2") (pintype "tri_state"))
    )
    (net (code "58") (name "Net-(LED225-C)") (class "Default")
      (node (ref "LED225") (pin "P$1") (pinfunction "C_P$1") (pintype "passive"))
      (node (ref "R203") (pin "2") (pinfunction "2_2") (pintype "passive"))
    )
    (net (code "59") (name "Net-(LED226-A)") (class "Default")
      (node (ref "LED226") (pin "P$2") (pinfunction "A_P$2") (pintype "passive"))
      (node (ref "U203") (pin "3") (pinfunction "QD_3") (pintype "tri_state"))
    )
    (net (code "60") (name "Net-(LED226-C)") (class "Default")
      (node (ref "LED226") (pin "P$1") (pinfunction "C_P$1") (pintype "passive"))
      (node (ref "R204") (pin "2") (pinfunction "2_2") (pintype "passive"))
    )
    (net (code "61") (name "Net-(LED227-A)") (class "Default")
      (node (ref "LED227") (pin "P$2") (pinfunction "A_P$2") (pintype "passive"))
      (node (ref "U203") (pin "4") (pinfunction "QE_4") (pintype "tri_state"))
    )
    (net (code "62") (name "Net-(LED227-C)") (class "Default")
      (node (ref "LED227") (pin "P$1") (pinfunction "C_P$1") (pintype "passive"))
      (node (ref "R205") (pin "2") (pinfunction "2_2") (pintype "passive"))
    )
    (net (code "63") (name "Net-(LED228-A)") (class "Default")
      (node (ref "LED228") (pin "P$2") (pinfunction "A_P$2") (pintype "passive"))
      (node (ref "U203") (pin "7") (pinfunction "QH_7") (pintype "tri_state"))
    )
    (net (code "64") (name "Net-(LED228-C)") (class "Default")
      (node (ref "LED228") (pin "P$1") (pinfunction "C_P$1") (pintype "passive"))
      (node (ref "R222") (pin "2") (pinfunction "2_2") (pintype "passive"))
    )
    (net (code "65") (name "Net-(LED229-C)") (class "Default")
      (node (ref "LED229") (pin "P$1") (pinfunction "C_P$1") (pintype "passive"))
      (node (ref "R223") (pin "2") (pinfunction "2_2") (pintype "passive"))
    )
    (net (code "66") (name "Net-(LED230-C)") (class "Default")
      (node (ref "LED230") (pin "P$1") (pinfunction "C_P$1") (pintype "passive"))
      (node (ref "R224") (pin "2") (pinfunction "2_2") (pintype "passive"))
    )
    (net (code "67") (name "Net-(LED231-C)") (class "Default")
      (node (ref "LED231") (pin "P$1") (pinfunction "C_P$1") (pintype "passive"))
      (node (ref "R225") (pin "2") (pinfunction "2_2") (pintype "passive"))
    )
    (net (code "68") (name "Net-(LED232-C)") (class "Default")
      (node (ref "LED232") (pin "P$1") (pinfunction "C_P$1") (pintype "passive"))
      (node (ref "R226") (pin "2") (pinfunction "2_2") (pintype "passive"))
    )
    (net (code "69") (name "Net-(LED233-C)") (class "Default")
      (node (ref "LED233") (pin "P$1") (pinfunction "C_P$1") (pintype "passive"))
      (node (ref "R227") (pin "2") (pinfunction "2_2") (pintype "passive"))
    )
    (net (code "70") (name "Net-(LED234-C)") (class "Default")
      (node (ref "LED234") (pin "P$1") (pinfunction "C_P$1") (pintype "passive"))
      (node (ref "R228") (pin "2") (pinfunction "2_2") (pintype "passive"))
    )
    (net (code "71") (name "Net-(LED235-C)") (class "Default")
      (node (ref "LED235") (pin "P$1") (pinfunction "C_P$1") (pintype "passive"))
      (node (ref "R229") (pin "2") (pinfunction "2_2") (pintype "passive"))
    )
    (net (code "72") (name "Net-(LED236-C)") (class "Default")
      (node (ref "LED236") (pin "P$1") (pinfunction "C_P$1") (pintype "passive"))
      (node (ref "R230") (pin "2") (pinfunction "2_2") (pintype "passive"))
    )
    (net (code "73") (name "Net-(T201-D)") (class "Default")
      (node (ref "R208") (pin "1") (pinfunction "1_1") (pintype "passive"))
      (node (ref "R209") (pin "1") (pinfunction "1_1") (pintype "passive"))
      (node (ref "R210") (pin "1") (pinfunction "1_1") (pintype "passive"))
      (node (ref "R211") (pin "1") (pinfunction "1_1") (pintype "passive"))
      (node (ref "R222") (pin "1") (pinfunction "1_1") (pintype "passive"))
      (node (ref "T201") (pin "1") (pinfunction "D_1") (pintype "passive"))
    )
    (net (code "74") (name "Net-(T201-G)") (class "Default")
      (node (ref "R240") (pin "2") (pinfunction "2_2") (pintype "passive"))
      (node (ref "T201") (pin "3") (pinfunction "G_3") (pintype "passive"))
    )
    (net (code "75") (name "Net-(T202-D)") (class "Default")
      (node (ref "R223") (pin "1") (pinfunction "1_1") (pintype "passive"))
      (node (ref "R224") (pin "1") (pinfunction "1_1") (pintype "passive"))
      (node (ref "R225") (pin "1") (pinfunction "1_1") (pintype "passive"))
      (node (ref "R226") (pin "1") (pinfunction "1_1") (pintype "passive"))
      (node (ref "R227") (pin "1") (pinfunction "1_1") (pintype "passive"))
      (node (ref "R228") (pin "1") (pinfunction "1_1") (pintype "passive"))
      (node (ref "R229") (pin "1") (pinfunction "1_1") (pintype "passive"))
      (node (ref "R230") (pin "1") (pinfunction "1_1") (pintype "passive"))
      (node (ref "R232") (pin "1") (pinfunction "1_1") (pintype "passive"))
      (node (ref "R233") (pin "1") (pinfunction "1_1") (pintype "passive"))
      (node (ref "R234") (pin "1") (pinfunction "1_1") (pintype "passive"))
      (node (ref "R235") (pin "1") (pinfunction "1_1") (pintype "passive"))
      (node (ref "R236") (pin "1") (pinfunction "1_1") (pintype "passive"))
      (node (ref "R237") (pin "1") (pinfunction "1_1") (pintype "passive"))
      (node (ref "R238") (pin "1") (pinfunction "1_1") (pintype "passive"))
      (node (ref "R239") (pin "1") (pinfunction "1_1") (pintype "passive"))
      (node (ref "T202") (pin "1") (pinfunction "D_1") (pintype "passive"))
    )
    (net (code "76") (name "Net-(T202-G)") (class "Default")
      (node (ref "R241") (pin "2") (pinfunction "2_2") (pintype "passive"))
      (node (ref "T202") (pin "3") (pinfunction "G_3") (pintype "passive"))
    )
    (net (code "77") (name "Net-(T203-D)") (class "Default")
      (node (ref "R201") (pin "1") (pinfunction "1_1") (pintype "passive"))
      (node (ref "R202") (pin "1") (pinfunction "1_1") (pintype "passive"))
      (node (ref "R212") (pin "1") (pinfunction "1_1") (pintype "passive"))
      (node (ref "R213") (pin "1") (pinfunction "1_1") (pintype "passive"))
      (node (ref "R221") (pin "1") (pinfunction "1_1") (pintype "passive"))
      (node (ref "T203") (pin "1") (pinfunction "D_1") (pintype "passive"))
    )
    (net (code "78") (name "Net-(T203-G)") (class "Default")
      (node (ref "R206") (pin "2") (pinfunction "2_2") (pintype "passive"))
      (node (ref "T203") (pin "3") (pinfunction "G_3") (pintype "passive"))
    )
    (net (code "79") (name "Net-(T204-D)") (class "Default")
      (node (ref "R216") (pin "1") (pinfunction "1_1") (pintype "passive"))
      (node (ref "R217") (pin "1") (pinfunction "1_1") (pintype "passive"))
      (node (ref "R218") (pin "1") (pinfunction "1_1") (pintype "passive"))
      (node (ref "R219") (pin "1") (pinfunction "1_1") (pintype "passive"))
      (node (ref "R220") (pin "1") (pinfunction "1_1") (pintype "passive"))
      (node (ref "T204") (pin "1") (pinfunction "D_1") (pintype "passive"))
    )
    (net (code "80") (name "Net-(T204-G)") (class "Default")
      (node (ref "R207") (pin "2") (pinfunction "2_2") (pintype "passive"))
      (node (ref "T204") (pin "3") (pinfunction "G_3") (pintype "passive"))
    )
    (net (code "81") (name "Net-(T205-D)") (class "Default")
      (node (ref "R203") (pin "1") (pinfunction "1_1") (pintype "passive"))
      (node (ref "R204") (pin "1") (pinfunction "1_1") (pintype "passive"))
      (node (ref "R205") (pin "1") (pinfunction "1_1") (pintype "passive"))
      (node (ref "R214") (pin "1") (pinfunction "1_1") (pintype "passive"))
      (node (ref "R215") (pin "1") (pinfunction "1_1") (pintype "passive"))
      (node (ref "T205") (pin "1") (pinfunction "D_1") (pintype "passive"))
    )
    (net (code "82") (name "Net-(T205-G)") (class "Default")
      (node (ref "R231") (pin "2") (pinfunction "2_2") (pintype "passive"))
      (node (ref "T205") (pin "3") (pinfunction "G_3") (pintype "passive"))
    )
    (net (code "83") (name "Net-(U102-RX0)") (class "Default")
      (node (ref "R101") (pin "1") (pinfunction "1_1") (pintype "passive"))
      (node (ref "U102") (pin "P$4") (pinfunction "RX0_P$4") (pintype "bidirectional"))
    )
    (net (code "84") (name "Net-(U102-RX1)") (class "Default")
      (node (ref "R102") (pin "1") (pinfunction "1_1") (pintype "passive"))
      (node (ref "U102") (pin "P$5") (pinfunction "RX1_P$5") (pintype "bidirectional"))
    )
    (net (code "85") (name "Net-(U102-RX2)") (class "Default")
      (node (ref "R103") (pin "1") (pinfunction "1_1") (pintype "passive"))
      (node (ref "U102") (pin "P$6") (pinfunction "RX2_P$6") (pintype "bidirectional"))
    )
    (net (code "86") (name "Net-(U102-RX3)") (class "Default")
      (node (ref "R104") (pin "1") (pinfunction "1_1") (pintype "passive"))
      (node (ref "U102") (pin "P$7") (pinfunction "RX3_P$7") (pintype "bidirectional"))
    )
    (net (code "87") (name "Net-(U102-RX4)") (class "Default")
      (node (ref "R105") (pin "1") (pinfunction "1_1") (pintype "passive"))
      (node (ref "U102") (pin "P$8") (pinfunction "RX4_P$8") (pintype "bidirectional"))
    )
    (net (code "88") (name "Net-(U102-VCAPA)") (class "Default")
      (node (ref "C102") (pin "1") (pinfunction "1_1") (pintype "passive"))
      (node (ref "U102") (pin "P$9") (pinfunction "VCAPA_P$9") (pintype "bidirectional"))
    )
    (net (code "89") (name "Net-(U102-VCAPD)") (class "Default")
      (node (ref "C104") (pin "1") (pinfunction "1_1") (pintype "passive"))
      (node (ref "U102") (pin "P$11") (pinfunction "VCAPD_P$11") (pintype "bidirectional"))
    )
    (net (code "90") (name "Net-(U201A-SER)") (class "Default")
      (node (ref "U201") (pin "14") (pinfunction "SER_14") (pintype "input"))
      (node (ref "U203") (pin "9") (pinfunction "QH*_9") (pintype "tri_state"))
    )
    (net (code "91") (name "Net-(U202A-QH*)") (class "Default")
      (node (ref "U202") (pin "9") (pinfunction "QH*_9") (pintype "tri_state"))
      (node (ref "U203") (pin "14") (pinfunction "SER_14") (pintype "input"))
    )
    (net (code "92") (name "RIGHT_RX") (class "Default")
      (node (ref "R101") (pin "2") (pinfunction "2_2") (pintype "passive"))
    )
    (net (code "93") (name "SR_CLK") (class "Default")
      (node (ref "TO_MAIN") (pin "17") (pinfunction "17_17") (pintype "bidirectional"))
      (node (ref "U201") (pin "11") (pinfunction "SCK_11") (pintype "input"))
      (node (ref "U201") (pin "12") (pinfunction "RCK_12") (pintype "input"))
      (node (ref "U202") (pin "11") (pinfunction "SCK_11") (pintype "input"))
      (node (ref "U202") (pin "12") (pinfunction "RCK_12") (pintype "input"))
      (node (ref "U203") (pin "11") (pinfunction "SCK_11") (pintype "input"))
      (node (ref "U203") (pin "12") (pinfunction "RCK_12") (pintype "input"))
    )
    (net (code "94") (name "SR_DATA") (class "Default")
      (node (ref "TO_MAIN") (pin "4") (pinfunction "4_4") (pintype "bidirectional"))
      (node (ref "U202") (pin "14") (pinfunction "SER_14") (pintype "input"))
    )
    (net (code "95") (name "TOP_RX") (class "Default")
      (node (ref "R105") (pin "2") (pinfunction "2_2") (pintype "passive"))
    )
    (net (code "96") (name "TX") (class "Default")
      (node (ref "U102") (pin "P$25") (pinfunction "TXD_P$25") (pintype "bidirectional"))
    )
    (net (code "97") (name "unconnected-(TO_MAIN-Pad8)") (class "Default")
      (node (ref "TO_MAIN") (pin "8") (pinfunction "8_8") (pintype "bidirectional"))
    )
    (net (code "98") (name "unconnected-(TO_MAIN-Pad9)") (class "Default")
      (node (ref "TO_MAIN") (pin "9") (pinfunction "9_9") (pintype "bidirectional"))
    )
    (net (code "99") (name "unconnected-(TO_MAIN-Pad12)") (class "Default")
      (node (ref "TO_MAIN") (pin "12") (pinfunction "12_12") (pintype "bidirectional"))
    )
    (net (code "100") (name "unconnected-(TO_MAIN-Pad13)") (class "Default")
      (node (ref "TO_MAIN") (pin "13") (pinfunction "13_13") (pintype "bidirectional"))
    )
    (net (code "101") (name "unconnected-(TO_MAIN-Pad14)") (class "Default")
      (node (ref "TO_MAIN") (pin "14") (pinfunction "14_14") (pintype "bidirectional"))
    )
    (net (code "102") (name "unconnected-(U102-EIO2-PadP$14)") (class "Default")
      (node (ref "U102") (pin "P$14") (pinfunction "EIO2_P$14") (pintype "bidirectional"))
    )
    (net (code "103") (name "unconnected-(U102-EIO3-PadP$19)") (class "Default")
      (node (ref "U102") (pin "P$19") (pinfunction "EIO3_P$19") (pintype "bidirectional"))
    )
    (net (code "104") (name "unconnected-(U102-NC-PadP$16)") (class "Default")
      (node (ref "U102") (pin "P$16") (pinfunction "NC_P$16") (pintype "bidirectional"))
    )
    (net (code "105") (name "unconnected-(U102-NC2-PadP$17)") (class "Default")
      (node (ref "U102") (pin "P$17") (pinfunction "NC2_P$17") (pintype "bidirectional"))
    )
    (net (code "106") (name "unconnected-(U102-NC3-PadP$18)") (class "Default")
      (node (ref "U102") (pin "P$18") (pinfunction "NC3_P$18") (pintype "bidirectional"))
    )
    (net (code "107") (name "unconnected-(U102-NC4-PadP$26)") (class "Default")
      (node (ref "U102") (pin "P$26") (pinfunction "NC4_P$26") (pintype "bidirectional"))
    )
    (net (code "108") (name "unconnected-(U102-SI2-PadP$22)") (class "Default")
      (node (ref "U102") (pin "P$22") (pinfunction "SI2_P$22") (pintype "bidirectional"))
    )
    (net (code "109") (name "unconnected-(U102-SI3-PadP$23)") (class "Default")
      (node (ref "U102") (pin "P$23") (pinfunction "SI3_P$23") (pintype "bidirectional"))
    )
    (net (code "110") (name "unconnected-(U102-VINDS-PadP$2)") (class "Default")
      (node (ref "U102") (pin "P$2") (pinfunction "VINDS_P$2") (pintype "bidirectional"))
    )
    (net (code "111") (name "unconnected-(U201A-QE-Pad4)") (class "Default")
      (node (ref "U201") (pin "4") (pinfunction "QE_4") (pintype "tri_state"))
    )
    (net (code "112") (name "unconnected-(U201A-QF-Pad5)") (class "Default")
      (node (ref "U201") (pin "5") (pinfunction "QF_5") (pintype "tri_state"))
    )
    (net (code "113") (name "unconnected-(U201A-QG-Pad6)") (class "Default")
      (node (ref "U201") (pin "6") (pinfunction "QG_6") (pintype "tri_state"))
    )
    (net (code "114") (name "unconnected-(U201A-QH*-Pad9)") (class "Default")
      (node (ref "U201") (pin "9") (pinfunction "QH*_9") (pintype "tri_state"))
    )
    (net (code "115") (name "unconnected-(U201A-QH-Pad7)") (class "Default")
      (node (ref "U201") (pin "7") (pinfunction "QH_7") (pintype "tri_state"))
    )
  )
)
